# VESC_POWER_SCH.net
KiCad netlist of a schematic drawn in Altium Designer
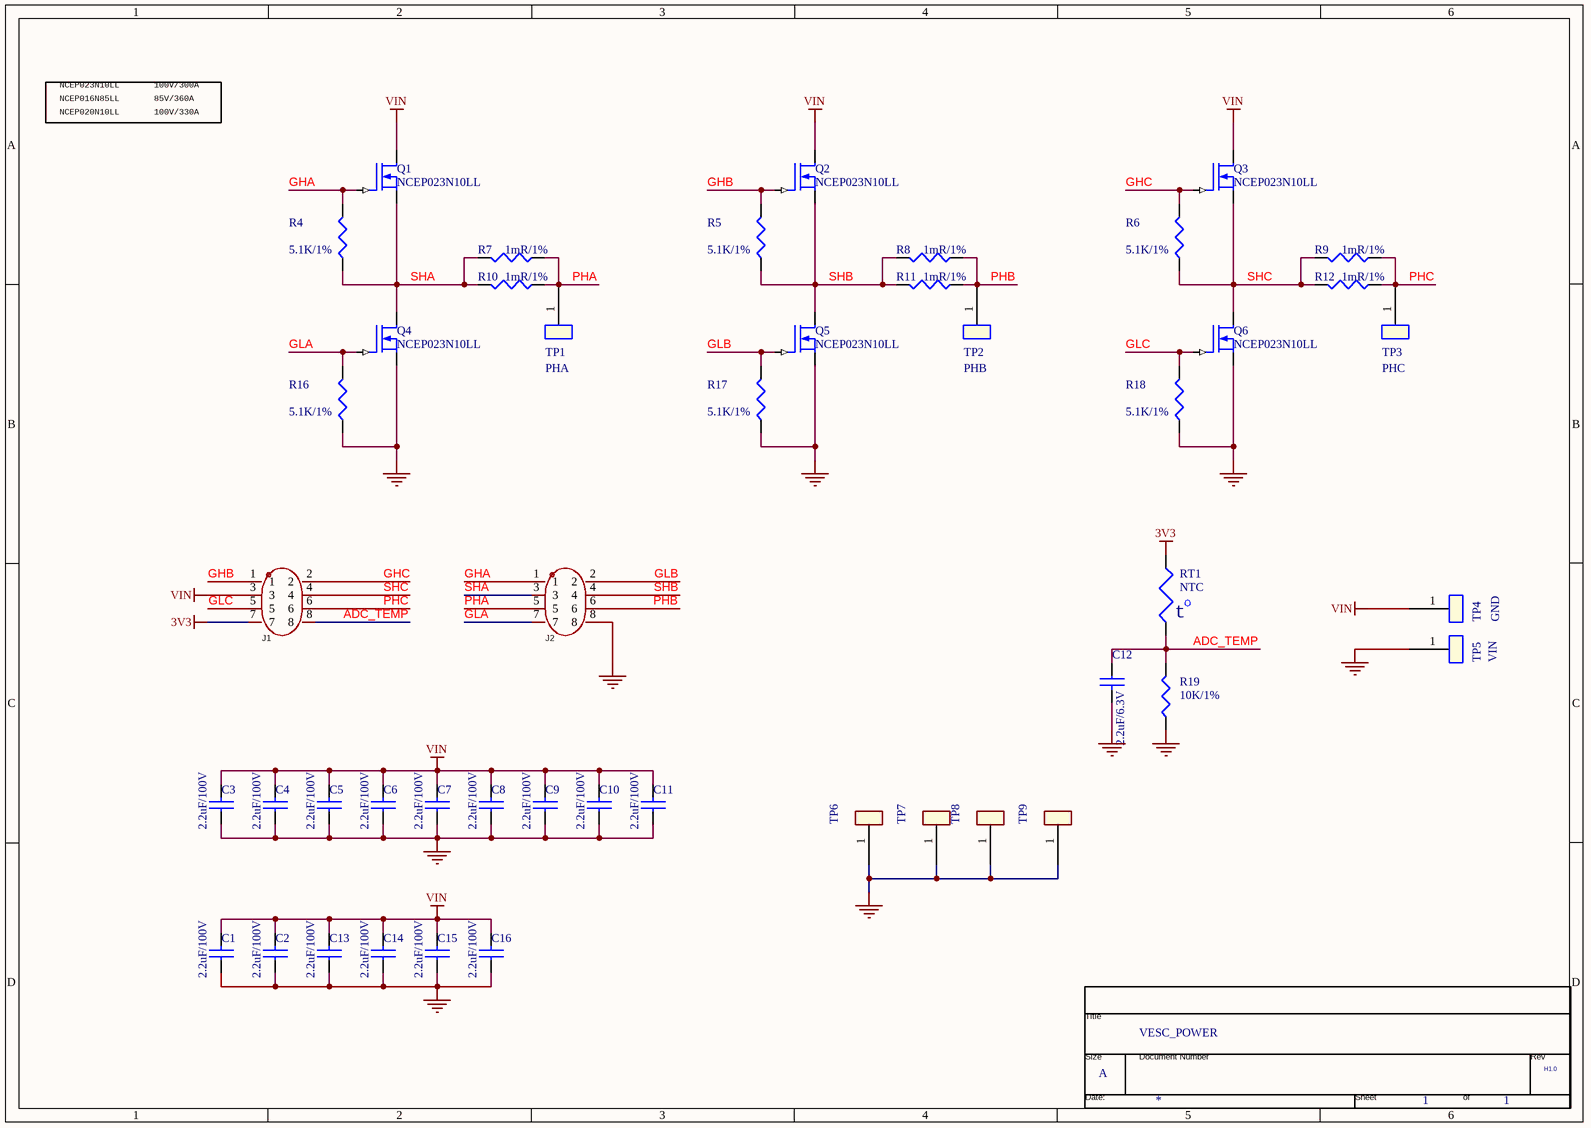
[diagram p0: VESC_POWER_SCH.SchDoc]

(export (version "E")
  (design (tool "Eeschema 10.0.6"))
  (components
    (comp (ref "*")
      (value "TitleBlock0")
      (fields
        (field (name "REVCODE") "H1.0")
        (field (name "TITLE") "VESC_POWER")
        (field (name "PAGE SIZE") "A")
        (field (name "PAGE NUMBER") "1")
        (field (name "PAGE COUNT") "1")
      )
      (libsource (lib "*") (part "TitleBlock0"))
    )
    (comp (ref "C1") (value "2.2uF/100V") (footprint "CAPC3225X230N") (libsource (lib "*") (part "CAP NP")))
    (comp (ref "C2") (value "2.2uF/100V") (footprint "CAPC3225X230N") (libsource (lib "*") (part "CAP NP")))
    (comp (ref "C3") (value "2.2uF/100V") (footprint "CAPC3225X230N") (libsource (lib "*") (part "CAP NP")))
    (comp (ref "C4") (value "2.2uF/100V") (footprint "CAPC3225X230N") (libsource (lib "*") (part "CAP NP")))
    (comp (ref "C5") (value "2.2uF/100V") (footprint "CAPC3225X230N") (libsource (lib "*") (part "CAP NP")))
    (comp (ref "C6") (value "2.2uF/100V") (footprint "CAPC3225X230N") (libsource (lib "*") (part "CAP NP")))
    (comp (ref "C7") (value "2.2uF/100V") (footprint "CAPC3225X230N") (libsource (lib "*") (part "CAP NP")))
    (comp (ref "C8") (value "2.2uF/100V") (footprint "CAPC3225X230N") (libsource (lib "*") (part "CAP NP")))
    (comp (ref "C9") (value "2.2uF/100V") (footprint "CAPC3225X230N") (libsource (lib "*") (part "CAP NP")))
    (comp (ref "C10") (value "2.2uF/100V") (footprint "CAPC3225X230N") (libsource (lib "*") (part "CAP NP")))
    (comp (ref "C11") (value "2.2uF/100V") (footprint "CAPC3225X230N") (libsource (lib "*") (part "CAP NP")))
    (comp (ref "C12") (value "2.2uF/6.3V") (footprint "C0603") (libsource (lib "*") (part "CAP NP")))
    (comp (ref "C13") (value "2.2uF/100V") (footprint "CAPC3225X230N") (libsource (lib "*") (part "CAP NP")))
    (comp (ref "C14") (value "2.2uF/100V") (footprint "CAPC3225X230N") (libsource (lib "*") (part "CAP NP")))
    (comp (ref "C15") (value "2.2uF/100V") (footprint "CAPC3225X230N") (libsource (lib "*") (part "CAP NP")))
    (comp (ref "C16") (value "2.2uF/100V") (footprint "CAPC3225X230N") (libsource (lib "*") (part "CAP NP")))
    (comp (ref "J1")
      (value "X6521WVS-2x04H-C60D74")
      (footprint "HDR-SMD_8P-P1.27-V-M-C2-C4-LS5.3")
      (fields (field (name "MANUFACTURER") "XKB Connection(中国星坤)"))
      (libsource (lib "VESC_POWER_Library") (part "X6521WVS-2x04H-C60D74"))
    )
    (comp (ref "J2")
      (value "X6521WVS-2x04H-C60D74")
      (footprint "HDR-SMD_8P-P1.27-V-M-C2-C4-LS5.3")
      (fields (field (name "MANUFACTURER") "XKB Connection(中国星坤)"))
      (libsource (lib "VESC_POWER_Library") (part "X6521WVS-2x04H-C60D74"))
    )
    (comp (ref "Q1") (value "NCEP023N10LL") (footprint "TOLL") (libsource (lib "*") (part "MOSFET N")))
    (comp (ref "Q2") (value "NCEP023N10LL") (footprint "TOLL") (libsource (lib "*") (part "MOSFET N")))
    (comp (ref "Q3") (value "NCEP023N10LL") (footprint "TOLL") (libsource (lib "*") (part "MOSFET N")))
    (comp (ref "Q4") (value "NCEP023N10LL") (footprint "TOLL") (libsource (lib "*") (part "MOSFET N")))
    (comp (ref "Q5") (value "NCEP023N10LL") (footprint "TOLL") (libsource (lib "*") (part "MOSFET N")))
    (comp (ref "Q6") (value "NCEP023N10LL") (footprint "TOLL") (libsource (lib "*") (part "MOSFET N")))
    (comp (ref "R4") (value "5.1K/1%") (footprint "R0603") (libsource (lib "*") (part "RESISTOR")))
    (comp (ref "R5") (value "5.1K/1%") (footprint "R0603") (libsource (lib "*") (part "RESISTOR")))
    (comp (ref "R6") (value "5.1K/1%") (footprint "R0603") (libsource (lib "*") (part "RESISTOR")))
    (comp (ref "R7") (value "1mR/1%") (footprint "R3920") (libsource (lib "*") (part "RESISTOR")))
    (comp (ref "R8") (value "1mR/1%") (footprint "R3920") (libsource (lib "*") (part "RESISTOR")))
    (comp (ref "R9") (value "1mR/1%") (footprint "R3920") (libsource (lib "*") (part "RESISTOR")))
    (comp (ref "R10") (value "1mR/1%") (footprint "R3920") (libsource (lib "*") (part "RESISTOR")))
    (comp (ref "R11") (value "1mR/1%") (footprint "R3920") (libsource (lib "*") (part "RESISTOR")))
    (comp (ref "R12") (value "1mR/1%") (footprint "R3920") (libsource (lib "*") (part "RESISTOR")))
    (comp (ref "R16") (value "5.1K/1%") (footprint "R0603") (libsource (lib "*") (part "RESISTOR")))
    (comp (ref "R17") (value "5.1K/1%") (footprint "R0603") (libsource (lib "*") (part "RESISTOR")))
    (comp (ref "R18") (value "5.1K/1%") (footprint "R0603") (libsource (lib "*") (part "RESISTOR")))
    (comp (ref "R19") (value "10K/1%") (footprint "R0603") (libsource (lib "*") (part "RESISTOR")))
    (comp (ref "RT1") (value "NTC") (footprint "R0603") (libsource (lib "*") (part "NTC")))
    (comp (ref "TP1") (value "PHA") (footprint "TP_8x8") (libsource (lib "") (part "TEST POINT_1")))
    (comp (ref "TP2") (value "PHB") (footprint "TP_8x8") (libsource (lib "") (part "TEST POINT_1")))
    (comp (ref "TP3") (value "PHC") (footprint "TP_8x8") (libsource (lib "") (part "TEST POINT_1")))
    (comp (ref "TP4") (value "GND") (footprint "TP_8x8") (libsource (lib "*") (part "TEST POINT")))
    (comp (ref "TP5") (value "VIN") (footprint "TP_8x8") (libsource (lib "*") (part "TEST POINT")))
    (comp (ref "TP6")
      (value "TEST POINT")
      (footprint "HOLE-3.2MM_M")
      (libsource (lib "VESC_POWER_Library") (part "TEST POINT"))
    )
    (comp (ref "TP7")
      (value "TEST POINT")
      (footprint "HOLE-3.2MM_M")
      (libsource (lib "VESC_POWER_Library") (part "TEST POINT"))
    )
    (comp (ref "TP8")
      (value "TEST POINT")
      (footprint "HOLE-3.2MM_M")
      (libsource (lib "VESC_POWER_Library") (part "TEST POINT"))
    )
    (comp (ref "TP9")
      (value "TEST POINT")
      (footprint "HOLE-3.2MM_M")
      (libsource (lib "VESC_POWER_Library") (part "TEST POINT"))
    )
  )
  (nets
    (net (code "1") (name "/ADC_TEMP") (class "Default")
      (node (ref "C12") (pin "1") (pinfunction "1_1") (pintype "passive"))
      (node (ref "J1") (pin "8") (pinfunction "8_8") (pintype "passive"))
      (node (ref "R19") (pin "2") (pinfunction "2_2") (pintype "passive"))
      (node (ref "RT1") (pin "2") (pinfunction "2_2") (pintype "passive"))
    )
    (net (code "2") (name "/GHA") (class "Default")
      (node (ref "J2") (pin "1") (pinfunction "1_1") (pintype "passive"))
      (node (ref "Q1") (pin "1") (pinfunction "GATE_1") (pintype "input"))
      (node (ref "R4") (pin "2") (pinfunction "2_2") (pintype "passive"))
    )
    (net (code "3") (name "/GHB") (class "Default")
      (node (ref "J1") (pin "1") (pinfunction "1_1") (pintype "passive"))
      (node (ref "Q2") (pin "1") (pinfunction "GATE_1") (pintype "input"))
      (node (ref "R5") (pin "2") (pinfunction "2_2") (pintype "passive"))
    )
    (net (code "4") (name "/GHC") (class "Default")
      (node (ref "J1") (pin "2") (pinfunction "2_2") (pintype "passive"))
      (node (ref "Q3") (pin "1") (pinfunction "GATE_1") (pintype "input"))
      (node (ref "R6") (pin "2") (pinfunction "2_2") (pintype "passive"))
    )
    (net (code "5") (name "/GLA") (class "Default")
      (node (ref "J2") (pin "7") (pinfunction "7_7") (pintype "passive"))
      (node (ref "Q4") (pin "1") (pinfunction "GATE_1") (pintype "input"))
      (node (ref "R16") (pin "2") (pinfunction "2_2") (pintype "passive"))
    )
    (net (code "6") (name "/GLB") (class "Default")
      (node (ref "J2") (pin "2") (pinfunction "2_2") (pintype "passive"))
      (node (ref "Q5") (pin "1") (pinfunction "GATE_1") (pintype "input"))
      (node (ref "R17") (pin "2") (pinfunction "2_2") (pintype "passive"))
    )
    (net (code "7") (name "/GLC") (class "Default")
      (node (ref "J1") (pin "5") (pinfunction "5_5") (pintype "passive"))
      (node (ref "Q6") (pin "1") (pinfunction "GATE_1") (pintype "input"))
      (node (ref "R18") (pin "2") (pinfunction "2_2") (pintype "passive"))
    )
    (net (code "8") (name "/PHA") (class "Default")
      (node (ref "J2") (pin "5") (pinfunction "5_5") (pintype "passive"))
      (node (ref "R10") (pin "1") (pinfunction "1_1") (pintype "passive"))
      (node (ref "R7") (pin "1") (pinfunction "1_1") (pintype "passive"))
      (node (ref "TP1") (pin "1") (pinfunction "1_1") (pintype "passive"))
    )
    (net (code "9") (name "/PHB") (class "Default")
      (node (ref "J2") (pin "6") (pinfunction "6_6") (pintype "passive"))
      (node (ref "R11") (pin "1") (pinfunction "1_1") (pintype "passive"))
      (node (ref "R8") (pin "1") (pinfunction "1_1") (pintype "passive"))
      (node (ref "TP2") (pin "1") (pinfunction "1_1") (pintype "passive"))
    )
    (net (code "10") (name "/PHC") (class "Default")
      (node (ref "J1") (pin "6") (pinfunction "6_6") (pintype "passive"))
      (node (ref "R12") (pin "1") (pinfunction "1_1") (pintype "passive"))
      (node (ref "R9") (pin "1") (pinfunction "1_1") (pintype "passive"))
      (node (ref "TP3") (pin "1") (pinfunction "1_1") (pintype "passive"))
    )
    (net (code "11") (name "/SHA") (class "Default")
      (node (ref "J2") (pin "3") (pinfunction "3_3") (pintype "passive"))
      (node (ref "Q1") (pin "3") (pinfunction "SOURCE_3") (pintype "passive"))
      (node (ref "Q4") (pin "2") (pinfunction "DRAIN_2") (pintype "passive"))
      (node (ref "R10") (pin "2") (pinfunction "2_2") (pintype "passive"))
      (node (ref "R4") (pin "1") (pinfunction "1_1") (pintype "passive"))
      (node (ref "R7") (pin "2") (pinfunction "2_2") (pintype "passive"))
    )
    (net (code "12") (name "/SHB") (class "Default")
      (node (ref "J2") (pin "4") (pinfunction "4_4") (pintype "passive"))
      (node (ref "Q2") (pin "3") (pinfunction "SOURCE_3") (pintype "passive"))
      (node (ref "Q5") (pin "2") (pinfunction "DRAIN_2") (pintype "passive"))
      (node (ref "R11") (pin "2") (pinfunction "2_2") (pintype "passive"))
      (node (ref "R5") (pin "1") (pinfunction "1_1") (pintype "passive"))
      (node (ref "R8") (pin "2") (pinfunction "2_2") (pintype "passive"))
    )
    (net (code "13") (name "/SHC") (class "Default")
      (node (ref "J1") (pin "4") (pinfunction "4_4") (pintype "passive"))
      (node (ref "Q3") (pin "3") (pinfunction "SOURCE_3") (pintype "passive"))
      (node (ref "Q6") (pin "2") (pinfunction "DRAIN_2") (pintype "passive"))
      (node (ref "R12") (pin "2") (pinfunction "2_2") (pintype "passive"))
      (node (ref "R6") (pin "1") (pinfunction "1_1") (pintype "passive"))
      (node (ref "R9") (pin "2") (pinfunction "2_2") (pintype "passive"))
    )
    (net (code "14") (name "3V3") (class "Default")
      (node (ref "J1") (pin "7") (pinfunction "7_7") (pintype "passive"))
      (node (ref "RT1") (pin "1") (pinfunction "1_1") (pintype "passive"))
    )
    (net (code "15") (name "GND") (class "Default")
      (node (ref "C1") (pin "1") (pinfunction "1_1") (pintype "passive"))
      (node (ref "C10") (pin "1") (pinfunction "1_1") (pintype "passive"))
      (node (ref "C11") (pin "1") (pinfunction "1_1") (pintype "passive"))
      (node (ref "C12") (pin "2") (pinfunction "2_2") (pintype "passive"))
      (node (ref "C13") (pin "1") (pinfunction "1_1") (pintype "passive"))
      (node (ref "C14") (pin "1") (pinfunction "1_1") (pintype "passive"))
      (node (ref "C15") (pin "1") (pinfunction "1_1") (pintype "passive"))
      (node (ref "C16") (pin "1") (pinfunction "1_1") (pintype "passive"))
      (node (ref "C2") (pin "1") (pinfunction "1_1") (pintype "passive"))
      (node (ref "C3") (pin "1") (pinfunction "1_1") (pintype "passive"))
      (node (ref "C4") (pin "1") (pinfunction "1_1") (pintype "passive"))
      (node (ref "C5") (pin "1") (pinfunction "1_1") (pintype "passive"))
      (node (ref "C6") (pin "1") (pinfunction "1_1") (pintype "passive"))
      (node (ref "C7") (pin "1") (pinfunction "1_1") (pintype "passive"))
      (node (ref "C8") (pin "1") (pinfunction "1_1") (pintype "passive"))
      (node (ref "C9") (pin "1") (pinfunction "1_1") (pintype "passive"))
      (node (ref "J2") (pin "8") (pinfunction "8_8") (pintype "passive"))
      (node (ref "Q4") (pin "3") (pinfunction "SOURCE_3") (pintype "passive"))
      (node (ref "Q5") (pin "3") (pinfunction "SOURCE_3") (pintype "passive"))
      (node (ref "Q6") (pin "3") (pinfunction "SOURCE_3") (pintype "passive"))
      (node (ref "R16") (pin "1") (pinfunction "1_1") (pintype "passive"))
      (node (ref "R17") (pin "1") (pinfunction "1_1") (pintype "passive"))
      (node (ref "R18") (pin "1") (pinfunction "1_1") (pintype "passive"))
      (node (ref "R19") (pin "1") (pinfunction "1_1") (pintype "passive"))
      (node (ref "TP5") (pin "1") (pinfunction "1_1") (pintype "passive"))
      (node (ref "TP6") (pin "1") (pinfunction "1_1") (pintype "passive"))
      (node (ref "TP7") (pin "1") (pinfunction "1_1") (pintype "passive"))
      (node (ref "TP8") (pin "1") (pinfunction "1_1") (pintype "passive"))
      (node (ref "TP9") (pin "1") (pinfunction "1_1") (pintype "passive"))
    )
    (net (code "16") (name "VIN") (class "Default")
      (node (ref "C1") (pin "2") (pinfunction "2_2") (pintype "passive"))
      (node (ref "C10") (pin "2") (pinfunction "2_2") (pintype "passive"))
      (node (ref "C11") (pin "2") (pinfunction "2_2") (pintype "passive"))
      (node (ref "C13") (pin "2") (pinfunction "2_2") (pintype "passive"))
      (node (ref "C14") (pin "2") (pinfunction "2_2") (pintype "passive"))
      (node (ref "C15") (pin "2") (pinfunction "2_2") (pintype "passive"))
      (node (ref "C16") (pin "2") (pinfunction "2_2") (pintype "passive"))
      (node (ref "C2") (pin "2") (pinfunction "2_2") (pintype "passive"))
      (node (ref "C3") (pin "2") (pinfunction "2_2") (pintype "passive"))
      (node (ref "C4") (pin "2") (pinfunction "2_2") (pintype "passive"))
      (node (ref "C5") (pin "2") (pinfunction "2_2") (pintype "passive"))
      (node (ref "C6") (pin "2") (pinfunction "2_2") (pintype "passive"))
      (node (ref "C7") (pin "2") (pinfunction "2_2") (pintype "passive"))
      (node (ref "C8") (pin "2") (pinfunction "2_2") (pintype "passive"))
      (node (ref "C9") (pin "2") (pinfunction "2_2") (pintype "passive"))
      (node (ref "J1") (pin "3") (pinfunction "3_3") (pintype "passive"))
      (node (ref "Q1") (pin "2") (pinfunction "DRAIN_2") (pintype "passive"))
      (node (ref "Q2") (pin "2") (pinfunction "DRAIN_2") (pintype "passive"))
      (node (ref "Q3") (pin "2") (pinfunction "DRAIN_2") (pintype "passive"))
      (node (ref "TP4") (pin "1") (pinfunction "1_1") (pintype "passive"))
    )
  )
)
